# NIXIE_4.net
KiCad netlist of a schematic drawn in Altium Designer
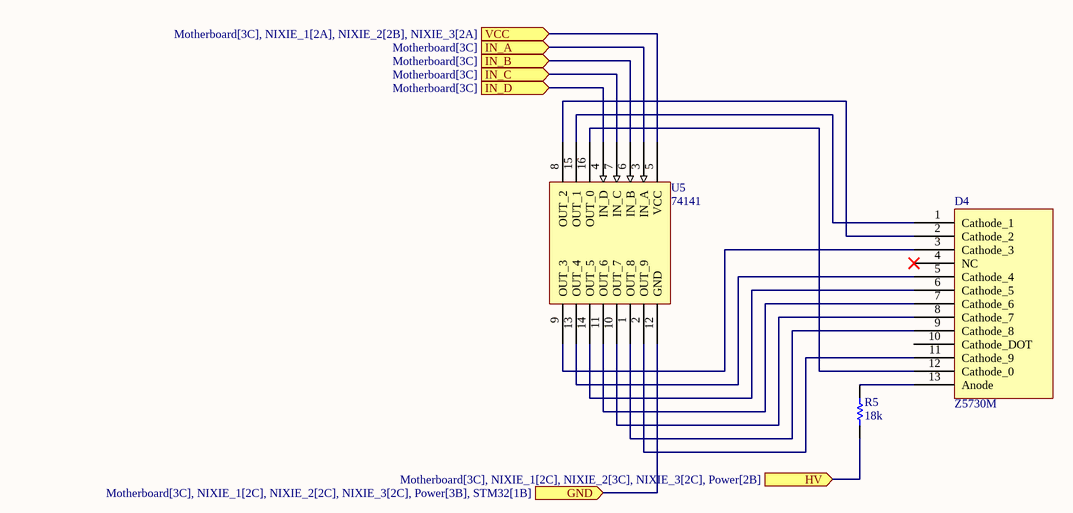
[diagram p0: NIXIE_4.SchDoc]

(export (version "E")
  (design (tool "Eeschema 10.0.6"))
  (components
    (comp (ref "D4") (value "Z5730M") (footprint "Z5730M") (libsource (lib "Z5730M") (part "Z5730M")))
    (comp (ref "R5")
      (value "18k")
      (footprint "RESC2013X60X40LL20T25")
      (fields (field (name "MANUFACTURER") "Panasonic") (field (name "PART NUMBER") "ERA6AEB183V"))
      (libsource (lib "Altium Content Vault") (part "RES"))
    )
    (comp (ref "U5") (value "74141") (footprint "DIP-16") (libsource (lib "Z5730M") (part "74141")))
  )
  (nets
    (net (code "1") (name "/GND") (class "Default")
      (node (ref "U5") (pin "12") (pinfunction "GND_12") (pintype "power_in"))
    )
    (net (code "2") (name "/HV") (class "Default")
      (node (ref "R5") (pin "1") (pinfunction "1_1") (pintype "passive"))
    )
    (net (code "3") (name "/IN_A") (class "Default")
      (node (ref "U5") (pin "3") (pinfunction "IN_A_3") (pintype "input"))
    )
    (net (code "4") (name "/IN_B") (class "Default")
      (node (ref "U5") (pin "6") (pinfunction "IN_B_6") (pintype "input"))
    )
    (net (code "5") (name "/IN_C") (class "Default")
      (node (ref "U5") (pin "7") (pinfunction "IN_C_7") (pintype "input"))
    )
    (net (code "6") (name "/IN_D") (class "Default")
      (node (ref "U5") (pin "4") (pinfunction "IN_D_4") (pintype "input"))
    )
    (net (code "7") (name "/VCC") (class "Default")
      (node (ref "U5") (pin "5") (pinfunction "VCC_5") (pintype "power_in"))
    )
    (net (code "8") (name "Net-(D4-Anode)") (class "Default")
      (node (ref "D4") (pin "13") (pinfunction "Anode_13") (pintype "passive"))
      (node (ref "R5") (pin "2") (pinfunction "2_2") (pintype "passive"))
    )
    (net (code "9") (name "Net-(D4-Cathode_0)") (class "Default")
      (node (ref "D4") (pin "12") (pinfunction "Cathode_0_12") (pintype "passive"))
      (node (ref "U5") (pin "16") (pinfunction "OUT_0_16") (pintype "open_collector"))
    )
    (net (code "10") (name "Net-(D4-Cathode_1)") (class "Default")
      (node (ref "D4") (pin "1") (pinfunction "Cathode_1_1") (pintype "passive"))
      (node (ref "U5") (pin "15") (pinfunction "OUT_1_15") (pintype "open_collector"))
    )
    (net (code "11") (name "Net-(D4-Cathode_2)") (class "Default")
      (node (ref "D4") (pin "2") (pinfunction "Cathode_2_2") (pintype "passive"))
      (node (ref "U5") (pin "8") (pinfunction "OUT_2_8") (pintype "open_collector"))
    )
    (net (code "12") (name "Net-(D4-Cathode_3)") (class "Default")
      (node (ref "D4") (pin "3") (pinfunction "Cathode_3_3") (pintype "passive"))
      (node (ref "U5") (pin "9") (pinfunction "OUT_3_9") (pintype "open_collector"))
    )
    (net (code "13") (name "Net-(D4-Cathode_4)") (class "Default")
      (node (ref "D4") (pin "5") (pinfunction "Cathode_4_5") (pintype "passive"))
      (node (ref "U5") (pin "13") (pinfunction "OUT_4_13") (pintype "open_collector"))
    )
    (net (code "14") (name "Net-(D4-Cathode_5)") (class "Default")
      (node (ref "D4") (pin "6") (pinfunction "Cathode_5_6") (pintype "passive"))
      (node (ref "U5") (pin "14") (pinfunction "OUT_5_14") (pintype "open_collector"))
    )
    (net (code "15") (name "Net-(D4-Cathode_6)") (class "Default")
      (node (ref "D4") (pin "7") (pinfunction "Cathode_6_7") (pintype "passive"))
      (node (ref "U5") (pin "11") (pinfunction "OUT_6_11") (pintype "open_collector"))
    )
    (net (code "16") (name "Net-(D4-Cathode_7)") (class "Default")
      (node (ref "D4") (pin "8") (pinfunction "Cathode_7_8") (pintype "passive"))
      (node (ref "U5") (pin "10") (pinfunction "OUT_7_10") (pintype "open_collector"))
    )
    (net (code "17") (name "Net-(D4-Cathode_8)") (class "Default")
      (node (ref "D4") (pin "9") (pinfunction "Cathode_8_9") (pintype "passive"))
      (node (ref "U5") (pin "1") (pinfunction "OUT_8_1") (pintype "open_collector"))
    )
    (net (code "18") (name "Net-(D4-Cathode_9)") (class "Default")
      (node (ref "D4") (pin "11") (pinfunction "Cathode_9_11") (pintype "passive"))
      (node (ref "U5") (pin "2") (pinfunction "OUT_9_2") (pintype "open_collector"))
    )
    (net (code "19") (name "unconnected-(D4-Cathode_DOT-Pad10)") (class "Default")
      (node (ref "D4") (pin "10") (pinfunction "Cathode_DOT_10") (pintype "passive"))
    )
    (net (code "20") (name "unconnected-(D4-NC-Pad4)") (class "Default")
      (node (ref "D4") (pin "4") (pinfunction "NC_4") (pintype "passive+no_connect"))
    )
  )
)
